# board_0_8v.net
KiCad netlist of a schematic drawn in EAGLE
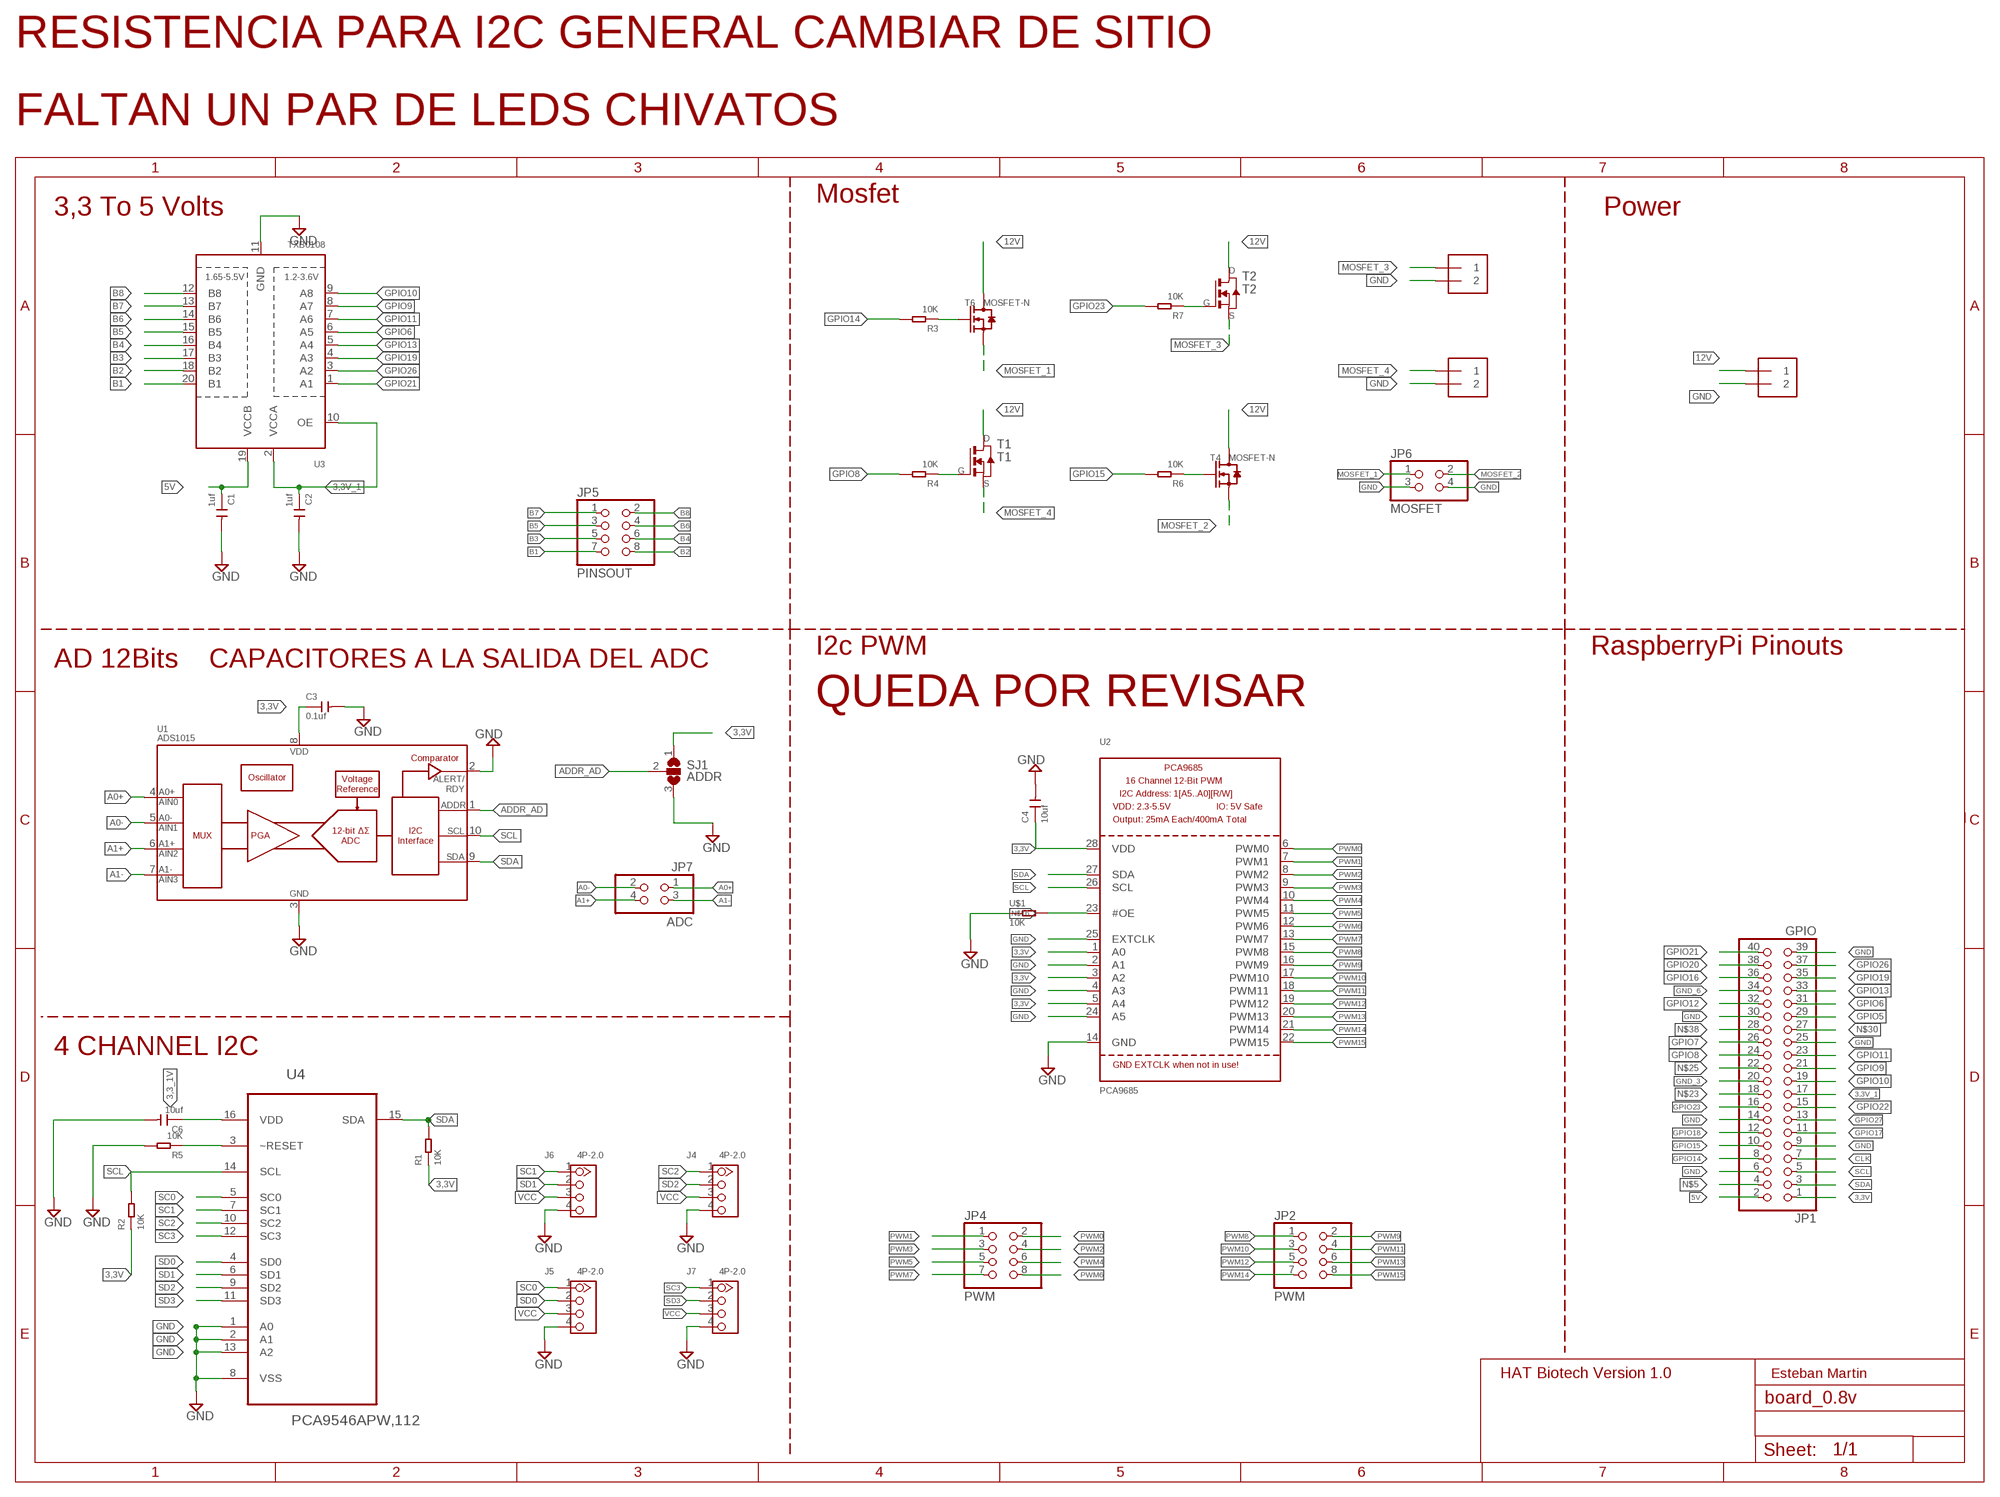
[diagram p0: schematic, sheet 1]

(export (version "E")
  (design (tool "Eeschema 10.0.6"))
  (components
    (comp (ref "C1")
      (value "1uf")
      (footprint "eagle-import:C0805")
      (fields (field (name "MPN") "CC0805KKX7R8BB105"))
      (libsource (lib "eagle-import") (part "CERAMIC-1UF-25V-10%-X7R(0805)"))
    )
    (comp (ref "C2")
      (value "1uf")
      (footprint "eagle-import:C0805")
      (fields (field (name "MPN") "CC0805KKX7R8BB105"))
      (libsource (lib "eagle-import") (part "CERAMIC-1UF-25V-10%-X7R(0805)"))
    )
    (comp (ref "C3")
      (value "0.1uf")
      (footprint "eagle-import:C0805")
      (fields (field (name "MPN") "CC0805KKX7R8BB105"))
      (libsource (lib "eagle-import") (part "CERAMIC-1UF-25V-10%-X7R(0805)"))
    )
    (comp (ref "C4")
      (value "10uf")
      (footprint "eagle-import:C0805")
      (fields (field (name "MPN") "CC0805KKX7R8BB105"))
      (libsource (lib "eagle-import") (part "CERAMIC-1UF-25V-10%-X7R(0805)"))
    )
    (comp (ref "C6")
      (value "10uf")
      (footprint "eagle-import:C0805")
      (fields (field (name "MPN") "CC0805KKX7R8BB105"))
      (libsource (lib "eagle-import") (part "CERAMIC-1UF-25V-10%-X7R(0805)"))
    )
    (comp (ref "J1")
      (value "1X2-3.5MM")
      (footprint "eagle-import:1X2-3.5MM")
      (libsource (lib "eagle-import") (part "1X2-3.5MM"))
    )
    (comp (ref "J2")
      (value "1X2-3.5MM")
      (footprint "eagle-import:1X2-3.5MM")
      (libsource (lib "eagle-import") (part "1X2-3.5MM"))
    )
    (comp (ref "J3")
      (value "1X2-3.5MM")
      (footprint "eagle-import:1X2-3.5MM")
      (libsource (lib "eagle-import") (part "1X2-3.5MM"))
    )
    (comp (ref "J4")
      (value "4P-2.0")
      (footprint "eagle-import:HW4-2.0")
      (libsource (lib "eagle-import") (part "GROVE-CONNECTOR-DIP(4P-2.0)"))
    )
    (comp (ref "J5")
      (value "4P-2.0")
      (footprint "eagle-import:HW4-2.0")
      (libsource (lib "eagle-import") (part "GROVE-CONNECTOR-DIP(4P-2.0)"))
    )
    (comp (ref "J6")
      (value "4P-2.0")
      (footprint "eagle-import:HW4-2.0")
      (libsource (lib "eagle-import") (part "GROVE-CONNECTOR-DIP(4P-2.0)"))
    )
    (comp (ref "J7")
      (value "4P-2.0")
      (footprint "eagle-import:HW4-2.0")
      (libsource (lib "eagle-import") (part "GROVE-CONNECTOR-DIP(4P-2.0)"))
    )
    (comp (ref "JP1")
      (value "GPIO")
      (footprint "eagle-import:2X20")
      (libsource (lib "eagle-import") (part "PINHD-2X20"))
    )
    (comp (ref "JP2")
      (value "PWM")
      (footprint "eagle-import:2X04")
      (libsource (lib "eagle-import") (part "PINHD-2X4"))
    )
    (comp (ref "JP4")
      (value "PWM")
      (footprint "eagle-import:2X04")
      (libsource (lib "eagle-import") (part "PINHD-2X4"))
    )
    (comp (ref "JP5")
      (value "PINSOUT")
      (footprint "eagle-import:2X04")
      (libsource (lib "eagle-import") (part "PINHD-2X4"))
    )
    (comp (ref "JP6")
      (value "MOSFET")
      (footprint "eagle-import:2X02")
      (libsource (lib "eagle-import") (part "PINHD-2X2"))
    )
    (comp (ref "JP7")
      (value "ADC")
      (footprint "eagle-import:2X02")
      (libsource (lib "eagle-import") (part "PINHD-2X2"))
    )
    (comp (ref "R1")
      (value "10K")
      (footprint "eagle-import:R0805")
      (fields (field (name "MPN") "RC0805FR-0710KL"))
      (libsource (lib "eagle-import") (part "SMD-RES-10K-1%-1/8W(0805)"))
    )
    (comp (ref "R2")
      (value "10K")
      (footprint "eagle-import:R0805")
      (fields (field (name "MPN") "RC0805FR-0710KL"))
      (libsource (lib "eagle-import") (part "SMD-RES-10K-1%-1/8W(0805)"))
    )
    (comp (ref "R3")
      (value "10K")
      (footprint "eagle-import:R0805")
      (fields (field (name "MPN") "RC0805FR-0710KL"))
      (libsource (lib "eagle-import") (part "SMD-RES-10K-1%-1/8W(0805)"))
    )
    (comp (ref "R4")
      (value "10K")
      (footprint "eagle-import:R0805")
      (fields (field (name "MPN") "RC0805FR-0710KL"))
      (libsource (lib "eagle-import") (part "SMD-RES-10K-1%-1/8W(0805)"))
    )
    (comp (ref "R5")
      (value "10K")
      (footprint "eagle-import:R0805")
      (fields (field (name "MPN") "RC0805FR-0710KL"))
      (libsource (lib "eagle-import") (part "SMD-RES-10K-1%-1/8W(0805)"))
    )
    (comp (ref "R6")
      (value "10K")
      (footprint "eagle-import:R0805")
      (fields (field (name "MPN") "RC0805FR-0710KL"))
      (libsource (lib "eagle-import") (part "SMD-RES-10K-1%-1/8W(0805)"))
    )
    (comp (ref "R7")
      (value "10K")
      (footprint "eagle-import:R0805")
      (fields (field (name "MPN") "RC0805FR-0710KL"))
      (libsource (lib "eagle-import") (part "SMD-RES-10K-1%-1/8W(0805)"))
    )
    (comp (ref "SJ1")
      (value "ADDR")
      (footprint "eagle-import:SJ_2")
      (libsource (lib "eagle-import") (part "SJ2W"))
    )
    (comp (ref "T1")
      (value "T1")
      (footprint "eagle-import:TO252")
      (libsource (lib "eagle-import") (part "NMOSFETTO252"))
    )
    (comp (ref "T2")
      (value "T2")
      (footprint "eagle-import:TO252")
      (libsource (lib "eagle-import") (part "NMOSFETTO252"))
    )
    (comp (ref "T4")
      (value "MOSFET-N")
      (footprint "eagle-import:SOT-23")
      (libsource (lib "eagle-import") (part "MOSFET-N"))
    )
    (comp (ref "T6")
      (value "MOSFET-N")
      (footprint "eagle-import:SOT-23")
      (libsource (lib "eagle-import") (part "MOSFET-N"))
    )
    (comp (ref "U$1")
      (value "10K")
      (footprint "eagle-import:R0805")
      (fields (field (name "MPN") "RC0805FR-0710KL"))
      (libsource (lib "eagle-import") (part "SMD-RES-10K-1%-1/8W(0805)"))
    )
    (comp (ref "U1")
      (value "ADS1015")
      (footprint "eagle-import:MSOP10")
      (libsource (lib "eagle-import") (part "ADS1015"))
    )
    (comp (ref "U2")
      (value "PCA9685")
      (footprint "eagle-import:TSSOP28")
      (libsource (lib "eagle-import") (part "PCA9685"))
    )
    (comp (ref "U3")
      (value "TXB0108")
      (footprint "eagle-import:TSSOP20")
      (libsource (lib "eagle-import") (part "TXB0108PWR"))
    )
    (comp (ref "U4")
      (value "PCA9546APW,112")
      (footprint "eagle-import:SOP65P640X110-16N")
      (libsource (lib "eagle-import") (part "PCA9546APW,112"))
    )
  )
  (nets
    (net (code "1") (name "3,3V") (class "Default")
      (node (ref "C3") (pin "1") (pinfunction "1_1") (pintype "passive"))
      (node (ref "C4") (pin "1") (pinfunction "1_1") (pintype "passive"))
      (node (ref "JP1") (pin "1") (pinfunction "1_1") (pintype "passive"))
      (node (ref "R1") (pin "1") (pinfunction "1_1") (pintype "passive"))
      (node (ref "R2") (pin "1") (pinfunction "1_1") (pintype "passive"))
      (node (ref "SJ1") (pin "1") (pinfunction "1_1") (pintype "passive"))
      (node (ref "U1") (pin "8") (pinfunction "VDD_8") (pintype "bidirectional"))
      (node (ref "U2") (pin "1") (pinfunction "A0_1") (pintype "bidirectional"))
      (node (ref "U2") (pin "28") (pinfunction "VDD_28") (pintype "power_in"))
      (node (ref "U2") (pin "3") (pinfunction "A2_3") (pintype "bidirectional"))
      (node (ref "U2") (pin "5") (pinfunction "A4_5") (pintype "bidirectional"))
    )
    (net (code "2") (name "3,3V_1") (class "Default")
      (node (ref "C2") (pin "1") (pinfunction "1_1") (pintype "passive"))
      (node (ref "JP1") (pin "17") (pinfunction "17_17") (pintype "passive"))
      (node (ref "U3") (pin "10") (pinfunction "OE_10") (pintype "bidirectional"))
      (node (ref "U3") (pin "2") (pinfunction "VCCA_2") (pintype "bidirectional"))
    )
    (net (code "3") (name "3,3_1V") (class "Default")
      (node (ref "C6") (pin "1") (pinfunction "1_1") (pintype "passive"))
      (node (ref "U4") (pin "16") (pinfunction "VDD_16") (pintype "power_in"))
    )
    (net (code "4") (name "5V") (class "Default")
      (node (ref "C1") (pin "1") (pinfunction "1_1") (pintype "passive"))
      (node (ref "JP1") (pin "2") (pinfunction "2_2") (pintype "passive"))
      (node (ref "U3") (pin "19") (pinfunction "VCCB_19") (pintype "bidirectional"))
    )
    (net (code "5") (name "12V") (class "Default")
      (node (ref "J2") (pin "1") (pinfunction "1_1") (pintype "passive"))
      (node (ref "T1") (pin "3") (pinfunction "D_3") (pintype "passive"))
      (node (ref "T2") (pin "3") (pinfunction "D_3") (pintype "passive"))
      (node (ref "T4") (pin "3") (pinfunction "D_3") (pintype "passive"))
      (node (ref "T6") (pin "3") (pinfunction "D_3") (pintype "passive"))
    )
    (net (code "6") (name "A0+") (class "Default")
      (node (ref "JP7") (pin "1") (pinfunction "1_1") (pintype "passive"))
      (node (ref "U1") (pin "4") (pinfunction "AIN0_4") (pintype "bidirectional"))
    )
    (net (code "7") (name "A0-") (class "Default")
      (node (ref "JP7") (pin "2") (pinfunction "2_2") (pintype "passive"))
      (node (ref "U1") (pin "5") (pinfunction "AIN1_5") (pintype "bidirectional"))
    )
    (net (code "8") (name "A1+") (class "Default")
      (node (ref "JP7") (pin "4") (pinfunction "4_4") (pintype "passive"))
      (node (ref "U1") (pin "6") (pinfunction "AIN2_6") (pintype "bidirectional"))
    )
    (net (code "9") (name "A1-") (class "Default")
      (node (ref "JP7") (pin "3") (pinfunction "3_3") (pintype "passive"))
      (node (ref "U1") (pin "7") (pinfunction "AIN3_7") (pintype "bidirectional"))
    )
    (net (code "10") (name "ADDR_AD") (class "Default")
      (node (ref "SJ1") (pin "2") (pinfunction "2_2") (pintype "passive"))
      (node (ref "U1") (pin "1") (pinfunction "ADDR_1") (pintype "bidirectional"))
    )
    (net (code "11") (name "B1") (class "Default")
      (node (ref "JP5") (pin "7") (pinfunction "7_7") (pintype "passive"))
      (node (ref "U3") (pin "20") (pinfunction "B1_20") (pintype "bidirectional"))
    )
    (net (code "12") (name "B2") (class "Default")
      (node (ref "JP5") (pin "8") (pinfunction "8_8") (pintype "passive"))
      (node (ref "U3") (pin "18") (pinfunction "B2_18") (pintype "bidirectional"))
    )
    (net (code "13") (name "B3") (class "Default")
      (node (ref "JP5") (pin "5") (pinfunction "5_5") (pintype "passive"))
      (node (ref "U3") (pin "17") (pinfunction "B3_17") (pintype "bidirectional"))
    )
    (net (code "14") (name "B4") (class "Default")
      (node (ref "JP5") (pin "6") (pinfunction "6_6") (pintype "passive"))
      (node (ref "U3") (pin "16") (pinfunction "B4_16") (pintype "bidirectional"))
    )
    (net (code "15") (name "B5") (class "Default")
      (node (ref "JP5") (pin "3") (pinfunction "3_3") (pintype "passive"))
      (node (ref "U3") (pin "15") (pinfunction "B5_15") (pintype "bidirectional"))
    )
    (net (code "16") (name "B6") (class "Default")
      (node (ref "JP5") (pin "4") (pinfunction "4_4") (pintype "passive"))
      (node (ref "U3") (pin "14") (pinfunction "B6_14") (pintype "bidirectional"))
    )
    (net (code "17") (name "B7") (class "Default")
      (node (ref "JP5") (pin "1") (pinfunction "1_1") (pintype "passive"))
      (node (ref "U3") (pin "13") (pinfunction "B7_13") (pintype "bidirectional"))
    )
    (net (code "18") (name "B8") (class "Default")
      (node (ref "JP5") (pin "2") (pinfunction "2_2") (pintype "passive"))
      (node (ref "U3") (pin "12") (pinfunction "B8_12") (pintype "bidirectional"))
    )
    (net (code "19") (name "CLK") (class "Default")
      (node (ref "JP1") (pin "7") (pinfunction "7_7") (pintype "passive"))
    )
    (net (code "20") (name "GND") (class "Default")
      (node (ref "C1") (pin "2") (pinfunction "2_2") (pintype "passive"))
      (node (ref "C2") (pin "2") (pinfunction "2_2") (pintype "passive"))
      (node (ref "C3") (pin "2") (pinfunction "2_2") (pintype "passive"))
      (node (ref "C4") (pin "2") (pinfunction "2_2") (pintype "passive"))
      (node (ref "C6") (pin "2") (pinfunction "2_2") (pintype "passive"))
      (node (ref "J1") (pin "2") (pinfunction "2_2") (pintype "passive"))
      (node (ref "J2") (pin "2") (pinfunction "2_2") (pintype "passive"))
      (node (ref "J3") (pin "2") (pinfunction "2_2") (pintype "passive"))
      (node (ref "J4") (pin "4") (pinfunction "4_4") (pintype "bidirectional"))
      (node (ref "J5") (pin "4") (pinfunction "4_4") (pintype "bidirectional"))
      (node (ref "J6") (pin "4") (pinfunction "4_4") (pintype "bidirectional"))
      (node (ref "J7") (pin "4") (pinfunction "4_4") (pintype "bidirectional"))
      (node (ref "JP1") (pin "14") (pinfunction "14_14") (pintype "passive"))
      (node (ref "JP1") (pin "25") (pinfunction "25_25") (pintype "passive"))
      (node (ref "JP1") (pin "30") (pinfunction "30_30") (pintype "passive"))
      (node (ref "JP1") (pin "39") (pinfunction "39_39") (pintype "passive"))
      (node (ref "JP1") (pin "6") (pinfunction "6_6") (pintype "passive"))
      (node (ref "JP1") (pin "9") (pinfunction "9_9") (pintype "passive"))
      (node (ref "JP6") (pin "3") (pinfunction "3_3") (pintype "passive"))
      (node (ref "JP6") (pin "4") (pinfunction "4_4") (pintype "passive"))
      (node (ref "R5") (pin "2") (pinfunction "2_2") (pintype "passive"))
      (node (ref "SJ1") (pin "3") (pinfunction "3_3") (pintype "passive"))
      (node (ref "U$1") (pin "1") (pinfunction "1_1") (pintype "passive"))
      (node (ref "U1") (pin "2") (pinfunction "ALERT/RDY_2") (pintype "bidirectional"))
      (node (ref "U1") (pin "3") (pinfunction "VSS_3") (pintype "bidirectional"))
      (node (ref "U2") (pin "14") (pinfunction "GND_14") (pintype "power_in"))
      (node (ref "U2") (pin "2") (pinfunction "A1_2") (pintype "bidirectional"))
      (node (ref "U2") (pin "24") (pinfunction "A5_24") (pintype "bidirectional"))
      (node (ref "U2") (pin "25") (pinfunction "EXTCLK_25") (pintype "input"))
      (node (ref "U2") (pin "4") (pinfunction "A3_4") (pintype "bidirectional"))
      (node (ref "U3") (pin "11") (pinfunction "GND_11") (pintype "bidirectional"))
      (node (ref "U4") (pin "1") (pinfunction "A0_1") (pintype "input"))
      (node (ref "U4") (pin "13") (pinfunction "A2_13") (pintype "input"))
      (node (ref "U4") (pin "2") (pinfunction "A1_2") (pintype "input"))
      (node (ref "U4") (pin "8") (pinfunction "VSS_8") (pintype "passive"))
    )
    (net (code "21") (name "GND_3") (class "Default")
      (node (ref "JP1") (pin "20") (pinfunction "20_20") (pintype "passive"))
    )
    (net (code "22") (name "GND_6") (class "Default")
      (node (ref "JP1") (pin "34") (pinfunction "34_34") (pintype "passive"))
    )
    (net (code "23") (name "GPIO5") (class "Default")
      (node (ref "JP1") (pin "29") (pinfunction "29_29") (pintype "passive"))
    )
    (net (code "24") (name "GPIO6") (class "Default")
      (node (ref "JP1") (pin "31") (pinfunction "31_31") (pintype "passive"))
      (node (ref "U3") (pin "6") (pinfunction "A5_6") (pintype "bidirectional"))
    )
    (net (code "25") (name "GPIO7") (class "Default")
      (node (ref "JP1") (pin "26") (pinfunction "26_26") (pintype "passive"))
    )
    (net (code "26") (name "GPIO8") (class "Default")
      (node (ref "JP1") (pin "24") (pinfunction "24_24") (pintype "passive"))
      (node (ref "R4") (pin "2") (pinfunction "2_2") (pintype "passive"))
    )
    (net (code "27") (name "GPIO9") (class "Default")
      (node (ref "JP1") (pin "21") (pinfunction "21_21") (pintype "passive"))
      (node (ref "U3") (pin "8") (pinfunction "A7_8") (pintype "bidirectional"))
    )
    (net (code "28") (name "GPIO10") (class "Default")
      (node (ref "JP1") (pin "19") (pinfunction "19_19") (pintype "passive"))
      (node (ref "U3") (pin "9") (pinfunction "A8_9") (pintype "bidirectional"))
    )
    (net (code "29") (name "GPIO11") (class "Default")
      (node (ref "JP1") (pin "23") (pinfunction "23_23") (pintype "passive"))
      (node (ref "U3") (pin "7") (pinfunction "A6_7") (pintype "bidirectional"))
    )
    (net (code "30") (name "GPIO12") (class "Default")
      (node (ref "JP1") (pin "32") (pinfunction "32_32") (pintype "passive"))
    )
    (net (code "31") (name "GPIO13") (class "Default")
      (node (ref "JP1") (pin "33") (pinfunction "33_33") (pintype "passive"))
      (node (ref "U3") (pin "5") (pinfunction "A4_5") (pintype "bidirectional"))
    )
    (net (code "32") (name "GPIO14") (class "Default")
      (node (ref "JP1") (pin "8") (pinfunction "8_8") (pintype "passive"))
      (node (ref "R3") (pin "2") (pinfunction "2_2") (pintype "passive"))
    )
    (net (code "33") (name "GPIO15") (class "Default")
      (node (ref "JP1") (pin "10") (pinfunction "10_10") (pintype "passive"))
      (node (ref "R6") (pin "2") (pinfunction "2_2") (pintype "passive"))
    )
    (net (code "34") (name "GPIO16") (class "Default")
      (node (ref "JP1") (pin "36") (pinfunction "36_36") (pintype "passive"))
    )
    (net (code "35") (name "GPIO17") (class "Default")
      (node (ref "JP1") (pin "11") (pinfunction "11_11") (pintype "passive"))
    )
    (net (code "36") (name "GPIO18") (class "Default")
      (node (ref "JP1") (pin "12") (pinfunction "12_12") (pintype "passive"))
    )
    (net (code "37") (name "GPIO19") (class "Default")
      (node (ref "JP1") (pin "35") (pinfunction "35_35") (pintype "passive"))
      (node (ref "U3") (pin "4") (pinfunction "A3_4") (pintype "bidirectional"))
    )
    (net (code "38") (name "GPIO20") (class "Default")
      (node (ref "JP1") (pin "38") (pinfunction "38_38") (pintype "passive"))
    )
    (net (code "39") (name "GPIO21") (class "Default")
      (node (ref "JP1") (pin "40") (pinfunction "40_40") (pintype "passive"))
      (node (ref "U3") (pin "1") (pinfunction "A1_1") (pintype "bidirectional"))
    )
    (net (code "40") (name "GPIO22") (class "Default")
      (node (ref "JP1") (pin "15") (pinfunction "15_15") (pintype "passive"))
    )
    (net (code "41") (name "GPIO23") (class "Default")
      (node (ref "JP1") (pin "16") (pinfunction "16_16") (pintype "passive"))
      (node (ref "R7") (pin "2") (pinfunction "2_2") (pintype "passive"))
    )
    (net (code "42") (name "GPIO26") (class "Default")
      (node (ref "JP1") (pin "37") (pinfunction "37_37") (pintype "passive"))
      (node (ref "U3") (pin "3") (pinfunction "A2_3") (pintype "bidirectional"))
    )
    (net (code "43") (name "GPIO27") (class "Default")
      (node (ref "JP1") (pin "13") (pinfunction "13_13") (pintype "passive"))
    )
    (net (code "44") (name "MOSFET_1") (class "Default")
      (node (ref "JP6") (pin "1") (pinfunction "1_1") (pintype "passive"))
      (node (ref "T6") (pin "2") (pinfunction "S_2") (pintype "passive"))
    )
    (net (code "45") (name "MOSFET_2") (class "Default")
      (node (ref "JP6") (pin "2") (pinfunction "2_2") (pintype "passive"))
      (node (ref "T4") (pin "2") (pinfunction "S_2") (pintype "passive"))
    )
    (net (code "46") (name "MOSFET_3") (class "Default")
      (node (ref "J1") (pin "1") (pinfunction "1_1") (pintype "passive"))
      (node (ref "T2") (pin "2") (pinfunction "S_2") (pintype "passive"))
    )
    (net (code "47") (name "MOSFET_4") (class "Default")
      (node (ref "J3") (pin "1") (pinfunction "1_1") (pintype "passive"))
      (node (ref "T1") (pin "2") (pinfunction "S_2") (pintype "passive"))
    )
    (net (code "48") (name "N$5") (class "Default")
      (node (ref "JP1") (pin "4") (pinfunction "4_4") (pintype "passive"))
    )
    (net (code "49") (name "N$16") (class "Default")
      (node (ref "U$1") (pin "2") (pinfunction "2_2") (pintype "passive"))
      (node (ref "U2") (pin "23") (pinfunction "#OE_23") (pintype "input"))
    )
    (net (code "50") (name "N$23") (class "Default")
      (node (ref "JP1") (pin "18") (pinfunction "18_18") (pintype "passive"))
    )
    (net (code "51") (name "N$25") (class "Default")
      (node (ref "JP1") (pin "22") (pinfunction "22_22") (pintype "passive"))
    )
    (net (code "52") (name "N$30") (class "Default")
      (node (ref "JP1") (pin "27") (pinfunction "27_27") (pintype "passive"))
    )
    (net (code "53") (name "N$38") (class "Default")
      (node (ref "JP1") (pin "28") (pinfunction "28_28") (pintype "passive"))
    )
    (net (code "54") (name "Net-(T1-G)") (class "Default")
      (node (ref "R4") (pin "1") (pinfunction "1_1") (pintype "passive"))
      (node (ref "T1") (pin "1") (pinfunction "G_1") (pintype "passive"))
    )
    (net (code "55") (name "Net-(T2-G)") (class "Default")
      (node (ref "R7") (pin "1") (pinfunction "1_1") (pintype "passive"))
      (node (ref "T2") (pin "1") (pinfunction "G_1") (pintype "passive"))
    )
    (net (code "56") (name "Net-(T4-G)") (class "Default")
      (node (ref "R6") (pin "1") (pinfunction "1_1") (pintype "passive"))
      (node (ref "T4") (pin "1") (pinfunction "G_1") (pintype "passive"))
    )
    (net (code "57") (name "Net-(T6-G)") (class "Default")
      (node (ref "R3") (pin "1") (pinfunction "1_1") (pintype "passive"))
      (node (ref "T6") (pin "1") (pinfunction "G_1") (pintype "passive"))
    )
    (net (code "58") (name "Net-(U4-~{RESET})") (class "Default")
      (node (ref "R5") (pin "1") (pinfunction "1_1") (pintype "passive"))
      (node (ref "U4") (pin "3") (pinfunction "~{RESET}_3") (pintype "input"))
    )
    (net (code "59") (name "PWM0") (class "Default")
      (node (ref "JP4") (pin "2") (pinfunction "2_2") (pintype "passive"))
      (node (ref "U2") (pin "6") (pinfunction "PWM0_6") (pintype "output"))
    )
    (net (code "60") (name "PWM1") (class "Default")
      (node (ref "JP4") (pin "1") (pinfunction "1_1") (pintype "passive"))
      (node (ref "U2") (pin "7") (pinfunction "PWM1_7") (pintype "output"))
    )
    (net (code "61") (name "PWM2") (class "Default")
      (node (ref "JP4") (pin "4") (pinfunction "4_4") (pintype "passive"))
      (node (ref "U2") (pin "8") (pinfunction "PWM2_8") (pintype "output"))
    )
    (net (code "62") (name "PWM3") (class "Default")
      (node (ref "JP4") (pin "3") (pinfunction "3_3") (pintype "passive"))
      (node (ref "U2") (pin "9") (pinfunction "PWM3_9") (pintype "output"))
    )
    (net (code "63") (name "PWM4") (class "Default")
      (node (ref "JP4") (pin "6") (pinfunction "6_6") (pintype "passive"))
      (node (ref "U2") (pin "10") (pinfunction "PWM4_10") (pintype "output"))
    )
    (net (code "64") (name "PWM5") (class "Default")
      (node (ref "JP4") (pin "5") (pinfunction "5_5") (pintype "passive"))
      (node (ref "U2") (pin "11") (pinfunction "PWM5_11") (pintype "output"))
    )
    (net (code "65") (name "PWM6") (class "Default")
      (node (ref "JP4") (pin "8") (pinfunction "8_8") (pintype "passive"))
      (node (ref "U2") (pin "12") (pinfunction "PWM6_12") (pintype "output"))
    )
    (net (code "66") (name "PWM7") (class "Default")
      (node (ref "JP4") (pin "7") (pinfunction "7_7") (pintype "passive"))
      (node (ref "U2") (pin "13") (pinfunction "PWM7_13") (pintype "output"))
    )
    (net (code "67") (name "PWM8") (class "Default")
      (node (ref "JP2") (pin "1") (pinfunction "1_1") (pintype "passive"))
      (node (ref "U2") (pin "15") (pinfunction "PWM8_15") (pintype "output"))
    )
    (net (code "68") (name "PWM9") (class "Default")
      (node (ref "JP2") (pin "2") (pinfunction "2_2") (pintype "passive"))
      (node (ref "U2") (pin "16") (pinfunction "PWM9_16") (pintype "output"))
    )
    (net (code "69") (name "PWM10") (class "Default")
      (node (ref "JP2") (pin "3") (pinfunction "3_3") (pintype "passive"))
      (node (ref "U2") (pin "17") (pinfunction "PWM10_17") (pintype "output"))
    )
    (net (code "70") (name "PWM11") (class "Default")
      (node (ref "JP2") (pin "4") (pinfunction "4_4") (pintype "passive"))
      (node (ref "U2") (pin "18") (pinfunction "PWM11_18") (pintype "output"))
    )
    (net (code "71") (name "PWM12") (class "Default")
      (node (ref "JP2") (pin "5") (pinfunction "5_5") (pintype "passive"))
      (node (ref "U2") (pin "19") (pinfunction "PWM12_19") (pintype "output"))
    )
    (net (code "72") (name "PWM13") (class "Default")
      (node (ref "JP2") (pin "6") (pinfunction "6_6") (pintype "passive"))
      (node (ref "U2") (pin "20") (pinfunction "PWM13_20") (pintype "output"))
    )
    (net (code "73") (name "PWM14") (class "Default")
      (node (ref "JP2") (pin "7") (pinfunction "7_7") (pintype "passive"))
      (node (ref "U2") (pin "21") (pinfunction "PWM14_21") (pintype "output"))
    )
    (net (code "74") (name "PWM15") (class "Default")
      (node (ref "JP2") (pin "8") (pinfunction "8_8") (pintype "passive"))
      (node (ref "U2") (pin "22") (pinfunction "PWM15_22") (pintype "output"))
    )
    (net (code "75") (name "SC0") (class "Default")
      (node (ref "J5") (pin "1") (pinfunction "1_1") (pintype "bidirectional"))
      (node (ref "U4") (pin "5") (pinfunction "SC0_5") (pintype "input"))
    )
    (net (code "76") (name "SC1") (class "Default")
      (node (ref "J6") (pin "1") (pinfunction "1_1") (pintype "bidirectional"))
      (node (ref "U4") (pin "7") (pinfunction "SC1_7") (pintype "input"))
    )
    (net (code "77") (name "SC2") (class "Default")
      (node (ref "J4") (pin "1") (pinfunction "1_1") (pintype "bidirectional"))
      (node (ref "U4") (pin "10") (pinfunction "SC2_10") (pintype "input"))
    )
    (net (code "78") (name "SC3") (class "Default")
      (node (ref "J7") (pin "1") (pinfunction "1_1") (pintype "bidirectional"))
      (node (ref "U4") (pin "12") (pinfunction "SC3_12") (pintype "input"))
    )
    (net (code "79") (name "SCL") (class "Default")
      (node (ref "JP1") (pin "5") (pinfunction "5_5") (pintype "passive"))
      (node (ref "R2") (pin "2") (pinfunction "2_2") (pintype "passive"))
      (node (ref "U1") (pin "10") (pinfunction "SCL_10") (pintype "bidirectional"))
      (node (ref "U2") (pin "26") (pinfunction "SCL_26") (pintype "bidirectional"))
      (node (ref "U4") (pin "14") (pinfunction "SCL_14") (pintype "bidirectional"))
    )
    (net (code "80") (name "SD0") (class "Default")
      (node (ref "J5") (pin "2") (pinfunction "2_2") (pintype "bidirectional"))
      (node (ref "U4") (pin "4") (pinfunction "SD0_4") (pintype "input"))
    )
    (net (code "81") (name "SD1") (class "Default")
      (node (ref "J6") (pin "2") (pinfunction "2_2") (pintype "bidirectional"))
      (node (ref "U4") (pin "6") (pinfunction "SD1_6") (pintype "input"))
    )
    (net (code "82") (name "SD2") (class "Default")
      (node (ref "J4") (pin "2") (pinfunction "2_2") (pintype "bidirectional"))
      (node (ref "U4") (pin "9") (pinfunction "SD2_9") (pintype "input"))
    )
    (net (code "83") (name "SD3") (class "Default")
      (node (ref "J7") (pin "2") (pinfunction "2_2") (pintype "bidirectional"))
      (node (ref "U4") (pin "11") (pinfunction "SD3_11") (pintype "input"))
    )
    (net (code "84") (name "SDA") (class "Default")
      (node (ref "JP1") (pin "3") (pinfunction "3_3") (pintype "passive"))
      (node (ref "R1") (pin "2") (pinfunction "2_2") (pintype "passive"))
      (node (ref "U1") (pin "9") (pinfunction "SDA_9") (pintype "bidirectional"))
      (node (ref "U2") (pin "27") (pinfunction "SDA_27") (pintype "bidirectional"))
      (node (ref "U4") (pin "15") (pinfunction "SDA_15") (pintype "bidirectional"))
    )
    (net (code "85") (name "VCC") (class "Default")
      (node (ref "J4") (pin "3") (pinfunction "3_3") (pintype "bidirectional"))
      (node (ref "J5") (pin "3") (pinfunction "3_3") (pintype "bidirectional"))
      (node (ref "J6") (pin "3") (pinfunction "3_3") (pintype "bidirectional"))
      (node (ref "J7") (pin "3") (pinfunction "3_3") (pintype "bidirectional"))
    )
  )
)
